# 8bit-quad-fc.net
KiCad netlist of a schematic drawn in EAGLE
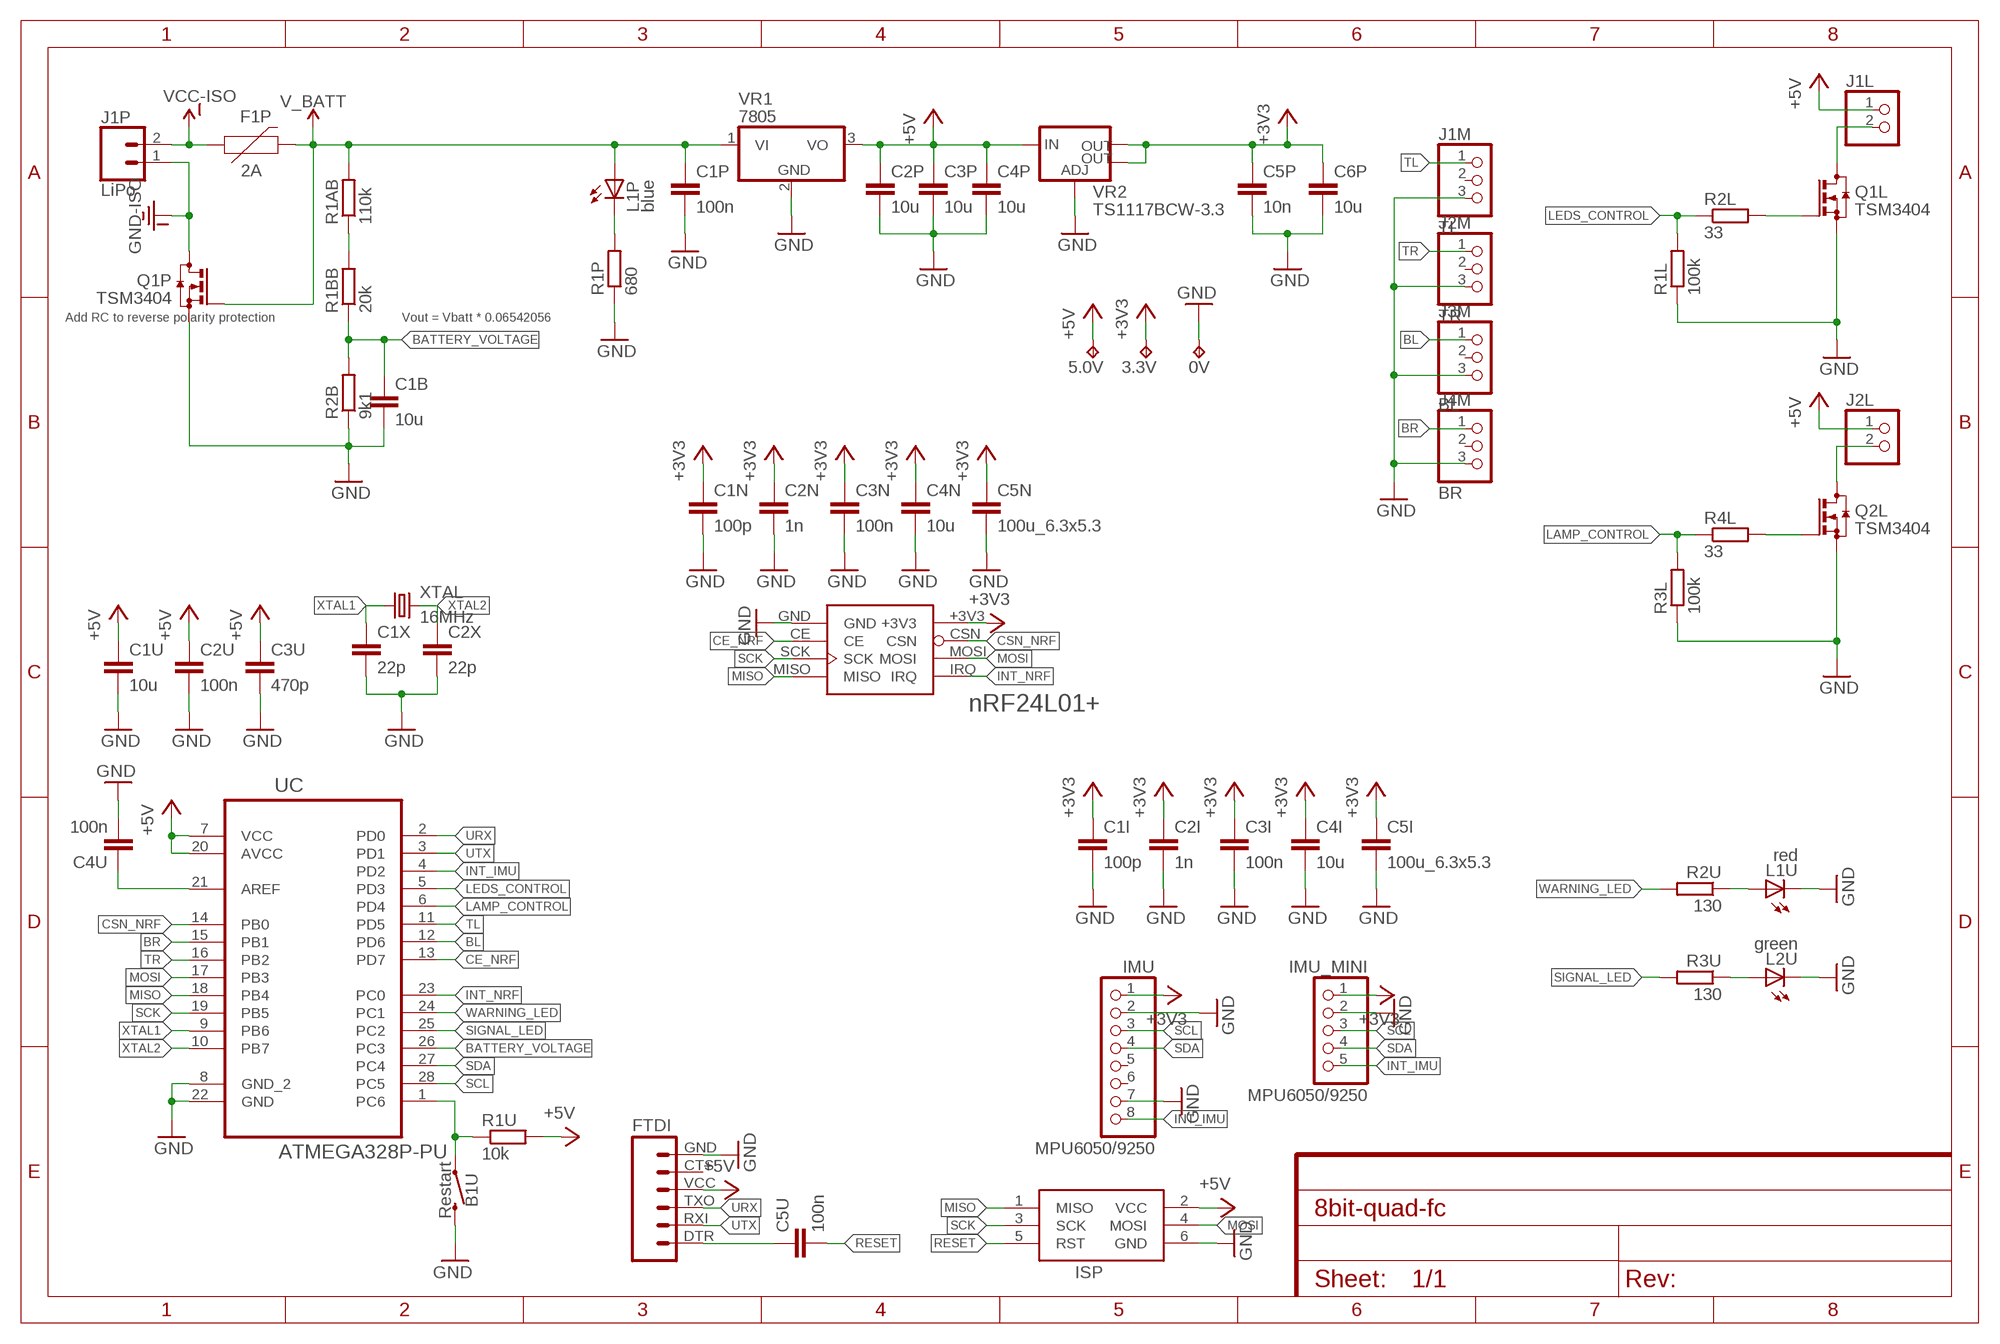
[diagram p0: schematic, sheet 1]

(export (version "E")
  (design (tool "Eeschema 10.0.6"))
  (components
    (comp (ref "0V")
      (value "TPTP10SQ")
      (footprint "eagle-import:TP10SQ")
      (libsource (lib "eagle-import") (part "TPTP10SQ"))
    )
    (comp (ref "3.3V")
      (value "TPTP10SQ")
      (footprint "eagle-import:TP10SQ")
      (libsource (lib "eagle-import") (part "TPTP10SQ"))
    )
    (comp (ref "5.0V")
      (value "TPTP10SQ")
      (footprint "eagle-import:TP10SQ")
      (libsource (lib "eagle-import") (part "TPTP10SQ"))
    )
    (comp (ref "B1U")
      (value "Restart")
      (footprint "eagle-import:TACTILE_SWITCH_PTH_6.0MM")
      (libsource (lib "eagle-import") (part "MOMENTARY-SWITCH-SPST-PTH-6.0MM"))
    )
    (comp (ref "C1B")
      (value "10u")
      (footprint "eagle-import:C1206")
      (libsource (lib "eagle-import") (part "C-EUC1206"))
    )
    (comp (ref "C1I")
      (value "100p")
      (footprint "eagle-import:C1206")
      (libsource (lib "eagle-import") (part "C-EUC1206"))
    )
    (comp (ref "C1N")
      (value "100p")
      (footprint "eagle-import:C1206")
      (libsource (lib "eagle-import") (part "C-EUC1206"))
    )
    (comp (ref "C1P")
      (value "100n")
      (footprint "eagle-import:C1206")
      (libsource (lib "eagle-import") (part "C-EUC1206"))
    )
    (comp (ref "C1U")
      (value "10u")
      (footprint "eagle-import:C1206")
      (libsource (lib "eagle-import") (part "C-EUC1206"))
    )
    (comp (ref "C1X")
      (value "22p")
      (footprint "eagle-import:C1206")
      (libsource (lib "eagle-import") (part "C-EUC1206"))
    )
    (comp (ref "C2I")
      (value "1n")
      (footprint "eagle-import:C1206")
      (fields (field (name "SPICEPREFIX") "C"))
      (libsource (lib "eagle-import") (part "C-EUC1206"))
    )
    (comp (ref "C2N")
      (value "1n")
      (footprint "eagle-import:C1206")
      (libsource (lib "eagle-import") (part "C-EUC1206"))
    )
    (comp (ref "C2P")
      (value "10u")
      (footprint "eagle-import:C1206")
      (libsource (lib "eagle-import") (part "C-EUC1206"))
    )
    (comp (ref "C2U")
      (value "100n")
      (footprint "eagle-import:C1206")
      (libsource (lib "eagle-import") (part "C-EUC1206"))
    )
    (comp (ref "C2X")
      (value "22p")
      (footprint "eagle-import:C1206")
      (libsource (lib "eagle-import") (part "C-EUC1206"))
    )
    (comp (ref "C3I")
      (value "100n")
      (footprint "eagle-import:C1206")
      (fields (field (name "SPICEPREFIX") "C"))
      (libsource (lib "eagle-import") (part "C-EUC1206"))
    )
    (comp (ref "C3N")
      (value "100n")
      (footprint "eagle-import:C1206")
      (libsource (lib "eagle-import") (part "C-EUC1206"))
    )
    (comp (ref "C3P")
      (value "10u")
      (footprint "eagle-import:C1206")
      (libsource (lib "eagle-import") (part "C-EUC1206"))
    )
    (comp (ref "C3U")
      (value "470p")
      (footprint "eagle-import:C1206")
      (libsource (lib "eagle-import") (part "C-EUC1206"))
    )
    (comp (ref "C4I")
      (value "10u")
      (footprint "eagle-import:C1206")
      (fields (field (name "SPICEPREFIX") "C"))
      (libsource (lib "eagle-import") (part "C-EUC1206"))
    )
    (comp (ref "C4N")
      (value "10u")
      (footprint "eagle-import:C1206")
      (libsource (lib "eagle-import") (part "C-EUC1206"))
    )
    (comp (ref "C4P")
      (value "10u")
      (footprint "eagle-import:C1206")
      (libsource (lib "eagle-import") (part "C-EUC1206"))
    )
    (comp (ref "C4U")
      (value "100n")
      (footprint "eagle-import:C1206")
      (libsource (lib "eagle-import") (part "C-EUC1206"))
    )
    (comp (ref "C5I")
      (value "100u_6.3x5.3")
      (footprint "eagle-import:C3225")
      (libsource (lib "eagle-import") (part "C-EUC3225"))
    )
    (comp (ref "C5N")
      (value "100u_6.3x5.3")
      (footprint "eagle-import:C3225")
      (libsource (lib "eagle-import") (part "C-EUC3225"))
    )
    (comp (ref "C5P")
      (value "10n")
      (footprint "eagle-import:C1206")
      (libsource (lib "eagle-import") (part "C-EUC1206"))
    )
    (comp (ref "C5U")
      (value "100n")
      (footprint "eagle-import:C1206")
      (libsource (lib "eagle-import") (part "C-EUC1206"))
    )
    (comp (ref "C6P")
      (value "10u")
      (footprint "eagle-import:C1206")
      (libsource (lib "eagle-import") (part "C-EUC1206"))
    )
    (comp (ref "F1P")
      (value "2A")
      (footprint "eagle-import:1206")
      (libsource (lib "eagle-import") (part "PPTC_HALF-AMP"))
    )
    (comp (ref "FTDI")
      (value "FTDI_BASICPTH")
      (footprint "eagle-import:FTDI_BASIC")
      (libsource (lib "eagle-import") (part "FTDI_BASICPTH"))
    )
    (comp (ref "IMU")
      (value "MPU6050/9250")
      (footprint "eagle-import:1X08")
      (libsource (lib "eagle-import") (part "PINHD-1X8_2.54"))
    )
    (comp (ref "IMU_MINI")
      (value "MPU6050/9250")
      (footprint "eagle-import:1X05")
      (libsource (lib "eagle-import") (part "PINHD-1X5"))
    )
    (comp (ref "ISP")
      (value "AVRISP-6")
      (footprint "eagle-import:AVRISP")
      (libsource (lib "eagle-import") (part "AVRISP-6"))
    )
    (comp (ref "J1L")
      (value "PINHD-1X2/90")
      (footprint "eagle-import:1X02_90")
      (libsource (lib "eagle-import") (part "PINHD-1X2/90"))
    )
    (comp (ref "J1M")
      (value "TL")
      (footprint "eagle-import:1X03_90")
      (libsource (lib "eagle-import") (part "PINHD-1X3/90"))
    )
    (comp (ref "J1P")
      (value "LiPo")
      (footprint "eagle-import:JST-2-PTH")
      (libsource (lib "eagle-import") (part "CONN_02JST-PTH-2"))
    )
    (comp (ref "J2L")
      (value "PINHD-1X2/90")
      (footprint "eagle-import:1X02_90")
      (libsource (lib "eagle-import") (part "PINHD-1X2/90"))
    )
    (comp (ref "J2M")
      (value "TR")
      (footprint "eagle-import:1X03_90")
      (libsource (lib "eagle-import") (part "PINHD-1X3/90"))
    )
    (comp (ref "J3M")
      (value "BL")
      (footprint "eagle-import:1X03_90")
      (libsource (lib "eagle-import") (part "PINHD-1X3/90"))
    )
    (comp (ref "J4M")
      (value "BR")
      (footprint "eagle-import:1X03_90")
      (libsource (lib "eagle-import") (part "PINHD-1X3/90"))
    )
    (comp (ref "L1P")
      (value "blue")
      (footprint "eagle-import:1206")
      (libsource (lib "eagle-import") (part "LEDSMT1206"))
    )
    (comp (ref "L1U")
      (value "red")
      (footprint "eagle-import:1206")
      (libsource (lib "eagle-import") (part "LEDSMT1206"))
    )
    (comp (ref "L2U")
      (value "green")
      (footprint "eagle-import:1206")
      (libsource (lib "eagle-import") (part "LEDSMT1206"))
    )
    (comp (ref "NRF24L01+")
      (value "nRF24L01+")
      (footprint "eagle-import:NRF24L01+_PA_LNA_SMD")
      (libsource (lib "eagle-import") (part "NRF24L01+_PA_LNA_BREAKOUT_SMD"))
    )
    (comp (ref "Q1L")
      (value "TSM3404")
      (footprint "eagle-import:SOT23")
      (libsource (lib "eagle-import") (part "BSS123"))
    )
    (comp (ref "Q1P")
      (value "TSM3404")
      (footprint "eagle-import:SOT23")
      (libsource (lib "eagle-import") (part "BSS123"))
    )
    (comp (ref "Q2L")
      (value "TSM3404")
      (footprint "eagle-import:SOT23")
      (libsource (lib "eagle-import") (part "BSS123"))
    )
    (comp (ref "R1AB")
      (value "110k")
      (footprint "eagle-import:R1206")
      (libsource (lib "eagle-import") (part "R-EU_R1206"))
    )
    (comp (ref "R1BB")
      (value "20k")
      (footprint "eagle-import:R1206")
      (libsource (lib "eagle-import") (part "R-EU_R1206"))
    )
    (comp (ref "R1L")
      (value "100k")
      (footprint "eagle-import:R1206")
      (libsource (lib "eagle-import") (part "R-EU_R1206"))
    )
    (comp (ref "R1P")
      (value "680")
      (footprint "eagle-import:R1206")
      (libsource (lib "eagle-import") (part "R-EU_R1206"))
    )
    (comp (ref "R1U")
      (value "10k")
      (footprint "eagle-import:R1206")
      (libsource (lib "eagle-import") (part "R-EU_R1206"))
    )
    (comp (ref "R2B")
      (value "9k1")
      (footprint "eagle-import:R1206")
      (libsource (lib "eagle-import") (part "R-EU_R1206"))
    )
    (comp (ref "R2L")
      (value "33")
      (footprint "eagle-import:R1206")
      (libsource (lib "eagle-import") (part "R-EU_R1206"))
    )
    (comp (ref "R2U")
      (value "130")
      (footprint "eagle-import:R1206")
      (libsource (lib "eagle-import") (part "R-EU_R1206"))
    )
    (comp (ref "R3L")
      (value "100k")
      (footprint "eagle-import:R1206")
      (libsource (lib "eagle-import") (part "R-EU_R1206"))
    )
    (comp (ref "R3U")
      (value "130")
      (footprint "eagle-import:R1206")
      (libsource (lib "eagle-import") (part "R-EU_R1206"))
    )
    (comp (ref "R4L")
      (value "33")
      (footprint "eagle-import:R1206")
      (libsource (lib "eagle-import") (part "R-EU_R1206"))
    )
    (comp (ref "UC")
      (value "ATMEGA328P-PU")
      (footprint "eagle-import:DIP254P762X457-28")
      (libsource (lib "eagle-import") (part "ATMEGA328P-PU"))
    )
    (comp (ref "VR1")
      (value "7805")
      (footprint "eagle-import:TO220V")
      (libsource (lib "eagle-import") (part "78TV05"))
    )
    (comp (ref "VR2")
      (value "TS1117BCW-3.3")
      (footprint "eagle-import:SOT223")
      (libsource (lib "eagle-import") (part "V_REG_LM1117SOT223"))
    )
    (comp (ref "XTAL")
      (value "16MHz")
      (footprint "eagle-import:HC49_S")
      (libsource (lib "eagle-import") (part "CRYSTALHC49S"))
    )
  )
  (nets
    (net (code "1") (name "+3V3") (class "Default")
      (node (ref "3.3V") (pin "TP") (pinfunction "TP_TP") (pintype "input"))
      (node (ref "C1I") (pin "1") (pinfunction "1_1") (pintype "passive"))
      (node (ref "C1N") (pin "1") (pinfunction "1_1") (pintype "passive"))
      (node (ref "C2I") (pin "1") (pinfunction "1_1") (pintype "passive"))
      (node (ref "C2N") (pin "1") (pinfunction "1_1") (pintype "passive"))
      (node (ref "C3I") (pin "1") (pinfunction "1_1") (pintype "passive"))
      (node (ref "C3N") (pin "1") (pinfunction "1_1") (pintype "passive"))
      (node (ref "C4I") (pin "1") (pinfunction "1_1") (pintype "passive"))
      (node (ref "C4N") (pin "1") (pinfunction "1_1") (pintype "passive"))
      (node (ref "C5I") (pin "1") (pinfunction "1_1") (pintype "passive"))
      (node (ref "C5N") (pin "1") (pinfunction "1_1") (pintype "passive"))
      (node (ref "C5P") (pin "1") (pinfunction "1_1") (pintype "passive"))
      (node (ref "C6P") (pin "1") (pinfunction "1_1") (pintype "passive"))
      (node (ref "IMU") (pin "1") (pinfunction "1_1") (pintype "passive"))
      (node (ref "IMU_MINI") (pin "1") (pinfunction "1_1") (pintype "passive"))
      (node (ref "NRF24L01+") (pin "+3V3") (pinfunction "+3V3_+3V3") (pintype "power_in"))
      (node (ref "VR2") (pin "2") (pinfunction "OUT_2") (pintype "output"))
      (node (ref "VR2") (pin "4") (pinfunction "OUT_4") (pintype "output"))
    )
    (net (code "2") (name "+5V") (class "Default")
      (node (ref "5.0V") (pin "TP") (pinfunction "TP_TP") (pintype "input"))
      (node (ref "C1U") (pin "1") (pinfunction "1_1") (pintype "passive"))
      (node (ref "C2P") (pin "1") (pinfunction "1_1") (pintype "passive"))
      (node (ref "C2U") (pin "1") (pinfunction "1_1") (pintype "passive"))
      (node (ref "C3P") (pin "1") (pinfunction "1_1") (pintype "passive"))
      (node (ref "C3U") (pin "1") (pinfunction "1_1") (pintype "passive"))
      (node (ref "C4P") (pin "1") (pinfunction "1_1") (pintype "passive"))
      (node (ref "FTDI") (pin "VCC") (pinfunction "4_VCC") (pintype "passive"))
      (node (ref "ISP") (pin "2") (pinfunction "VCC_2") (pintype "power_in"))
      (node (ref "J1L") (pin "1") (pinfunction "1_1") (pintype "passive"))
      (node (ref "J2L") (pin "1") (pinfunction "1_1") (pintype "passive"))
      (node (ref "R1U") (pin "2") (pinfunction "2_2") (pintype "passive"))
      (node (ref "UC") (pin "20") (pinfunction "AVCC_20") (pintype "power_in"))
      (node (ref "UC") (pin "7") (pinfunction "VCC_7") (pintype "power_in"))
      (node (ref "VR1") (pin "3") (pinfunction "VO_3") (pintype "passive"))
      (node (ref "VR2") (pin "3") (pinfunction "IN_3") (pintype "input"))
    )
    (net (code "3") (name "BATTERY_VOLTAGE") (class "Default")
      (node (ref "C1B") (pin "1") (pinfunction "1_1") (pintype "passive"))
      (node (ref "R1BB") (pin "1") (pinfunction "1_1") (pintype "passive"))
      (node (ref "R2B") (pin "2") (pinfunction "2_2") (pintype "passive"))
      (node (ref "UC") (pin "26") (pinfunction "PC3_26") (pintype "bidirectional"))
    )
    (net (code "4") (name "BL") (class "Default")
      (node (ref "J3M") (pin "1") (pinfunction "1_1") (pintype "passive"))
      (node (ref "UC") (pin "12") (pinfunction "PD6_12") (pintype "bidirectional"))
    )
    (net (code "5") (name "BR") (class "Default")
      (node (ref "J4M") (pin "1") (pinfunction "1_1") (pintype "passive"))
      (node (ref "UC") (pin "15") (pinfunction "PB1_15") (pintype "bidirectional"))
    )
    (net (code "6") (name "CE_NRF") (class "Default")
      (node (ref "NRF24L01+") (pin "CE") (pinfunction "CE_CE") (pintype "input"))
      (node (ref "UC") (pin "13") (pinfunction "PD7_13") (pintype "bidirectional"))
    )
    (net (code "7") (name "CSN_NRF") (class "Default")
      (node (ref "NRF24L01+") (pin "CSN") (pinfunction "CSN_CSN") (pintype "input"))
      (node (ref "UC") (pin "14") (pinfunction "PB0_14") (pintype "bidirectional"))
    )
    (net (code "8") (name "GND") (class "Default")
      (node (ref "0V") (pin "TP") (pinfunction "TP_TP") (pintype "input"))
      (node (ref "B1U") (pin "3") (pinfunction "2_3") (pintype "passive"))
      (node (ref "C1B") (pin "2") (pinfunction "2_2") (pintype "passive"))
      (node (ref "C1I") (pin "2") (pinfunction "2_2") (pintype "passive"))
      (node (ref "C1N") (pin "2") (pinfunction "2_2") (pintype "passive"))
      (node (ref "C1P") (pin "2") (pinfunction "2_2") (pintype "passive"))
      (node (ref "C1U") (pin "2") (pinfunction "2_2") (pintype "passive"))
      (node (ref "C1X") (pin "2") (pinfunction "2_2") (pintype "passive"))
      (node (ref "C2I") (pin "2") (pinfunction "2_2") (pintype "passive"))
      (node (ref "C2N") (pin "2") (pinfunction "2_2") (pintype "passive"))
      (node (ref "C2P") (pin "2") (pinfunction "2_2") (pintype "passive"))
      (node (ref "C2U") (pin "2") (pinfunction "2_2") (pintype "passive"))
      (node (ref "C2X") (pin "2") (pinfunction "2_2") (pintype "passive"))
      (node (ref "C3I") (pin "2") (pinfunction "2_2") (pintype "passive"))
      (node (ref "C3N") (pin "2") (pinfunction "2_2") (pintype "passive"))
      (node (ref "C3P") (pin "2") (pinfunction "2_2") (pintype "passive"))
      (node (ref "C3U") (pin "2") (pinfunction "2_2") (pintype "passive"))
      (node (ref "C4I") (pin "2") (pinfunction "2_2") (pintype "passive"))
      (node (ref "C4N") (pin "2") (pinfunction "2_2") (pintype "passive"))
      (node (ref "C4P") (pin "2") (pinfunction "2_2") (pintype "passive"))
      (node (ref "C4U") (pin "2") (pinfunction "2_2") (pintype "passive"))
      (node (ref "C5I") (pin "2") (pinfunction "2_2") (pintype "passive"))
      (node (ref "C5N") (pin "2") (pinfunction "2_2") (pintype "passive"))
      (node (ref "C5P") (pin "2") (pinfunction "2_2") (pintype "passive"))
      (node (ref "C6P") (pin "2") (pinfunction "2_2") (pintype "passive"))
      (node (ref "FTDI") (pin "GND") (pinfunction "6_GND") (pintype "passive"))
      (node (ref "IMU") (pin "2") (pinfunction "2_2") (pintype "passive"))
      (node (ref "IMU") (pin "7") (pinfunction "7_7") (pintype "passive"))
      (node (ref "IMU_MINI") (pin "2") (pinfunction "2_2") (pintype "passive"))
      (node (ref "ISP") (pin "6") (pinfunction "GND_6") (pintype "power_in"))
      (node (ref "J1M") (pin "3") (pinfunction "3_3") (pintype "passive"))
      (node (ref "J2M") (pin "3") (pinfunction "3_3") (pintype "passive"))
      (node (ref "J3M") (pin "3") (pinfunction "3_3") (pintype "passive"))
      (node (ref "J4M") (pin "3") (pinfunction "3_3") (pintype "passive"))
      (node (ref "L1U") (pin "C") (pinfunction "C_C") (pintype "passive"))
      (node (ref "L2U") (pin "C") (pinfunction "C_C") (pintype "passive"))
      (node (ref "NRF24L01+") (pin "GND") (pinfunction "GND_GND") (pintype "power_in"))
      (node (ref "Q1L") (pin "2") (pinfunction "S_2") (pintype "passive"))
      (node (ref "Q1P") (pin "2") (pinfunction "S_2") (pintype "passive"))
      (node (ref "Q2L") (pin "2") (pinfunction "S_2") (pintype "passive"))
      (node (ref "R1L") (pin "1") (pinfunction "1_1") (pintype "passive"))
      (node (ref "R1P") (pin "1") (pinfunction "1_1") (pintype "passive"))
      (node (ref "R2B") (pin "1") (pinfunction "1_1") (pintype "passive"))
      (node (ref "R3L") (pin "1") (pinfunction "1_1") (pintype "passive"))
      (node (ref "UC") (pin "22") (pinfunction "GND_22") (pintype "passive"))
      (node (ref "UC") (pin "8") (pinfunction "GND_2_8") (pintype "passive"))
      (node (ref "VR1") (pin "2") (pinfunction "GND_2") (pintype "passive"))
      (node (ref "VR2") (pin "1") (pinfunction "ADJ_1") (pintype "input"))
    )
    (net (code "9") (name "GND-ISO") (class "Default")
      (node (ref "J1P") (pin "1") (pinfunction "1_1") (pintype "passive"))
      (node (ref "Q1P") (pin "3") (pinfunction "D_3") (pintype "passive"))
    )
    (net (code "10") (name "INT_IMU") (class "Default")
      (node (ref "IMU") (pin "8") (pinfunction "8_8") (pintype "passive"))
      (node (ref "IMU_MINI") (pin "5") (pinfunction "5_5") (pintype "passive"))
      (node (ref "UC") (pin "4") (pinfunction "PD2_4") (pintype "bidirectional"))
    )
    (net (code "11") (name "INT_NRF") (class "Default")
      (node (ref "NRF24L01+") (pin "IRQ") (pinfunction "IRQ_IRQ") (pintype "output"))
      (node (ref "UC") (pin "23") (pinfunction "PC0_23") (pintype "bidirectional"))
    )
    (net (code "12") (name "LAMP_CONTROL") (class "Default")
      (node (ref "R3L") (pin "2") (pinfunction "2_2") (pintype "passive"))
      (node (ref "R4L") (pin "1") (pinfunction "1_1") (pintype "passive"))
      (node (ref "UC") (pin "6") (pinfunction "PD4_6") (pintype "bidirectional"))
    )
    (net (code "13") (name "LEDS_CONTROL") (class "Default")
      (node (ref "R1L") (pin "2") (pinfunction "2_2") (pintype "passive"))
      (node (ref "R2L") (pin "1") (pinfunction "1_1") (pintype "passive"))
      (node (ref "UC") (pin "5") (pinfunction "PD3_5") (pintype "bidirectional"))
    )
    (net (code "14") (name "MISO") (class "Default")
      (node (ref "ISP") (pin "1") (pinfunction "MISO_1") (pintype "input"))
      (node (ref "NRF24L01+") (pin "MISO") (pinfunction "MISO_MISO") (pintype "output"))
      (node (ref "UC") (pin "18") (pinfunction "PB4_18") (pintype "bidirectional"))
    )
    (net (code "15") (name "MOSI") (class "Default")
      (node (ref "ISP") (pin "4") (pinfunction "MOSI_4") (pintype "output"))
      (node (ref "NRF24L01+") (pin "MOSI") (pinfunction "MOSI_MOSI") (pintype "input"))
      (node (ref "UC") (pin "17") (pinfunction "PB3_17") (pintype "bidirectional"))
    )
    (net (code "16") (name "Net-(FTDI-1)") (class "Default")
      (node (ref "C5U") (pin "1") (pinfunction "1_1") (pintype "passive"))
      (node (ref "FTDI") (pin "DTR") (pinfunction "1_DTR") (pintype "passive"))
    )
    (net (code "17") (name "Net-(L1P-PadC)") (class "Default")
      (node (ref "L1P") (pin "C") (pinfunction "C_C") (pintype "passive"))
      (node (ref "R1P") (pin "2") (pinfunction "2_2") (pintype "passive"))
    )
    (net (code "18") (name "Net-(L1U-PadA)") (class "Default")
      (node (ref "L1U") (pin "A") (pinfunction "A_A") (pintype "passive"))
      (node (ref "R2U") (pin "1") (pinfunction "1_1") (pintype "passive"))
    )
    (net (code "19") (name "Net-(L2U-PadA)") (class "Default")
      (node (ref "L2U") (pin "A") (pinfunction "A_A") (pintype "passive"))
      (node (ref "R3U") (pin "1") (pinfunction "1_1") (pintype "passive"))
    )
    (net (code "20") (name "Net-(Q1L-D)") (class "Default")
      (node (ref "J1L") (pin "2") (pinfunction "2_2") (pintype "passive"))
      (node (ref "Q1L") (pin "3") (pinfunction "D_3") (pintype "passive"))
    )
    (net (code "21") (name "Net-(Q1L-G)") (class "Default")
      (node (ref "Q1L") (pin "1") (pinfunction "G_1") (pintype "passive"))
      (node (ref "R2L") (pin "2") (pinfunction "2_2") (pintype "passive"))
    )
    (net (code "22") (name "Net-(Q2L-D)") (class "Default")
      (node (ref "J2L") (pin "2") (pinfunction "2_2") (pintype "passive"))
      (node (ref "Q2L") (pin "3") (pinfunction "D_3") (pintype "passive"))
    )
    (net (code "23") (name "Net-(Q2L-G)") (class "Default")
      (node (ref "Q2L") (pin "1") (pinfunction "G_1") (pintype "passive"))
      (node (ref "R4L") (pin "2") (pinfunction "2_2") (pintype "passive"))
    )
    (net (code "24") (name "Net-(R1AB-Pad1)") (class "Default")
      (node (ref "R1AB") (pin "1") (pinfunction "1_1") (pintype "passive"))
      (node (ref "R1BB") (pin "2") (pinfunction "2_2") (pintype "passive"))
    )
    (net (code "25") (name "Net-(UC-AREF)") (class "Default")
      (node (ref "C4U") (pin "1") (pinfunction "1_1") (pintype "passive"))
      (node (ref "UC") (pin "21") (pinfunction "AREF_21") (pintype "input"))
    )
    (net (code "26") (name "RESET") (class "Default")
      (node (ref "B1U") (pin "1") (pinfunction "1_1") (pintype "passive"))
      (node (ref "C5U") (pin "2") (pinfunction "2_2") (pintype "passive"))
      (node (ref "ISP") (pin "5") (pinfunction "RST_5") (pintype "output"))
      (node (ref "R1U") (pin "1") (pinfunction "1_1") (pintype "passive"))
      (node (ref "UC") (pin "1") (pinfunction "PC6_1") (pintype "bidirectional"))
    )
    (net (code "27") (name "SCK") (class "Default")
      (node (ref "ISP") (pin "3") (pinfunction "SCK_3") (pintype "output"))
      (node (ref "NRF24L01+") (pin "SCK") (pinfunction "SCK_SCK") (pintype "input"))
      (node (ref "UC") (pin "19") (pinfunction "PB5_19") (pintype "bidirectional"))
    )
    (net (code "28") (name "SCL") (class "Default")
      (node (ref "IMU") (pin "3") (pinfunction "3_3") (pintype "passive"))
      (node (ref "IMU_MINI") (pin "3") (pinfunction "3_3") (pintype "passive"))
      (node (ref "UC") (pin "28") (pinfunction "PC5_28") (pintype "bidirectional"))
    )
    (net (code "29") (name "SDA") (class "Default")
      (node (ref "IMU") (pin "4") (pinfunction "4_4") (pintype "passive"))
      (node (ref "IMU_MINI") (pin "4") (pinfunction "4_4") (pintype "passive"))
      (node (ref "UC") (pin "27") (pinfunction "PC4_27") (pintype "bidirectional"))
    )
    (net (code "30") (name "SIGNAL_LED") (class "Default")
      (node (ref "R3U") (pin "2") (pinfunction "2_2") (pintype "passive"))
      (node (ref "UC") (pin "25") (pinfunction "PC2_25") (pintype "bidirectional"))
    )
    (net (code "31") (name "TL") (class "Default")
      (node (ref "J1M") (pin "1") (pinfunction "1_1") (pintype "passive"))
      (node (ref "UC") (pin "11") (pinfunction "PD5_11") (pintype "bidirectional"))
    )
    (net (code "32") (name "TR") (class "Default")
      (node (ref "J2M") (pin "1") (pinfunction "1_1") (pintype "passive"))
      (node (ref "UC") (pin "16") (pinfunction "PB2_16") (pintype "bidirectional"))
    )
    (net (code "33") (name "URX") (class "Default")
      (node (ref "FTDI") (pin "TXO") (pinfunction "3_TXO") (pintype "passive"))
      (node (ref "UC") (pin "2") (pinfunction "PD0_2") (pintype "bidirectional"))
    )
    (net (code "34") (name "UTX") (class "Default")
      (node (ref "FTDI") (pin "RXI") (pinfunction "2_RXI") (pintype "passive"))
      (node (ref "UC") (pin "3") (pinfunction "PD1_3") (pintype "bidirectional"))
    )
    (net (code "35") (name "VCC-ISO") (class "Default")
      (node (ref "F1P") (pin "1") (pinfunction "1_1") (pintype "bidirectional"))
      (node (ref "J1P") (pin "2") (pinfunction "2_2") (pintype "passive"))
    )
    (net (code "36") (name "V_BATT") (class "Default")
      (node (ref "C1P") (pin "1") (pinfunction "1_1") (pintype "passive"))
      (node (ref "F1P") (pin "2") (pinfunction "2_2") (pintype "bidirectional"))
      (node (ref "L1P") (pin "A") (pinfunction "A_A") (pintype "passive"))
      (node (ref "Q1P") (pin "1") (pinfunction "G_1") (pintype "passive"))
      (node (ref "R1AB") (pin "2") (pinfunction "2_2") (pintype "passive"))
      (node (ref "VR1") (pin "1") (pinfunction "VI_1") (pintype "input"))
    )
    (net (code "37") (name "WARNING_LED") (class "Default")
      (node (ref "R2U") (pin "2") (pinfunction "2_2") (pintype "passive"))
      (node (ref "UC") (pin "24") (pinfunction "PC1_24") (pintype "bidirectional"))
    )
    (net (code "38") (name "XTAL1") (class "Default")
      (node (ref "C1X") (pin "1") (pinfunction "1_1") (pintype "passive"))
      (node (ref "UC") (pin "9") (pinfunction "PB6_9") (pintype "bidirectional"))
      (node (ref "XTAL") (pin "1") (pinfunction "1_1") (pintype "passive"))
    )
    (net (code "39") (name "XTAL2") (class "Default")
      (node (ref "C2X") (pin "1") (pinfunction "1_1") (pintype "passive"))
      (node (ref "UC") (pin "10") (pinfunction "PB7_10") (pintype "bidirectional"))
      (node (ref "XTAL") (pin "2") (pinfunction "2_2") (pintype "passive"))
    )
    (net (code "40") (name "unconnected-(FTDI-5-PadCTS)") (class "Default")
      (node (ref "FTDI") (pin "CTS") (pinfunction "5_CTS") (pintype "passive"))
    )
    (net (code "41") (name "unconnected-(IMU-Pad5)") (class "Default")
      (node (ref "IMU") (pin "5") (pinfunction "5_5") (pintype "passive"))
    )
    (net (code "42") (name "unconnected-(IMU-Pad6)") (class "Default")
      (node (ref "IMU") (pin "6") (pinfunction "6_6") (pintype "passive"))
    )
    (net (code "43") (name "unconnected-(J1M-Pad2)") (class "Default")
      (node (ref "J1M") (pin "2") (pinfunction "2_2") (pintype "passive"))
    )
    (net (code "44") (name "unconnected-(J2M-Pad2)") (class "Default")
      (node (ref "J2M") (pin "2") (pinfunction "2_2") (pintype "passive"))
    )
    (net (code "45") (name "unconnected-(J3M-Pad2)") (class "Default")
      (node (ref "J3M") (pin "2") (pinfunction "2_2") (pintype "passive"))
    )
    (net (code "46") (name "unconnected-(J4M-Pad2)") (class "Default")
      (node (ref "J4M") (pin "2") (pinfunction "2_2") (pintype "passive"))
    )
  )
)
